# sloth_final.net
KiCad netlist of a schematic drawn in EAGLE
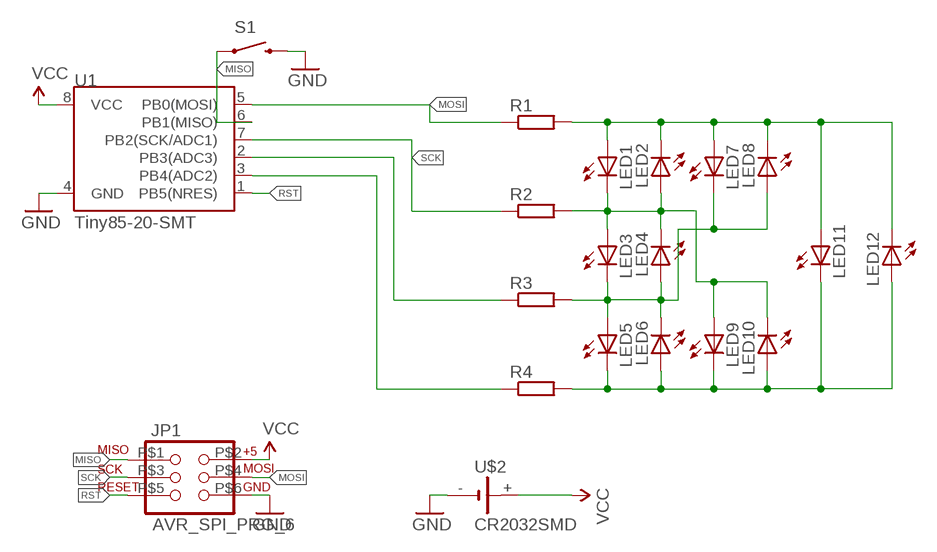
[diagram p0: schematic, sheet 1]

(export (version "E")
  (design (tool "Eeschema 10.0.6"))
  (components
    (comp (ref "JP1")
      (value "AVR_SPI_PRG_6")
      (footprint "eagle-import:2X3_SMD_PAD")
      (libsource (lib "eagle-import") (part "AVR_SPI_PRG_6"))
    )
    (comp (ref "LED1")
      (value "LEDCHIP-LED0805")
      (footprint "eagle-import:CHIP-LED0805")
      (libsource (lib "eagle-import") (part "LEDCHIP-LED0805"))
    )
    (comp (ref "LED2")
      (value "LEDCHIP-LED0805")
      (footprint "eagle-import:CHIP-LED0805")
      (libsource (lib "eagle-import") (part "LEDCHIP-LED0805"))
    )
    (comp (ref "LED3")
      (value "LEDCHIP-LED0805")
      (footprint "eagle-import:CHIP-LED0805")
      (libsource (lib "eagle-import") (part "LEDCHIP-LED0805"))
    )
    (comp (ref "LED4")
      (value "LEDCHIP-LED0805")
      (footprint "eagle-import:CHIP-LED0805")
      (libsource (lib "eagle-import") (part "LEDCHIP-LED0805"))
    )
    (comp (ref "LED5")
      (value "LEDCHIP-LED0805")
      (footprint "eagle-import:CHIP-LED0805")
      (libsource (lib "eagle-import") (part "LEDCHIP-LED0805"))
    )
    (comp (ref "LED6")
      (value "LEDCHIP-LED0805")
      (footprint "eagle-import:CHIP-LED0805")
      (libsource (lib "eagle-import") (part "LEDCHIP-LED0805"))
    )
    (comp (ref "LED7")
      (value "LEDCHIP-LED0805")
      (footprint "eagle-import:CHIP-LED0805")
      (libsource (lib "eagle-import") (part "LEDCHIP-LED0805"))
    )
    (comp (ref "LED8")
      (value "LEDCHIP-LED0805")
      (footprint "eagle-import:CHIP-LED0805")
      (libsource (lib "eagle-import") (part "LEDCHIP-LED0805"))
    )
    (comp (ref "LED9")
      (value "LEDCHIP-LED0805")
      (footprint "eagle-import:CHIP-LED0805")
      (libsource (lib "eagle-import") (part "LEDCHIP-LED0805"))
    )
    (comp (ref "LED10")
      (value "LEDCHIP-LED0805")
      (footprint "eagle-import:CHIP-LED0805")
      (libsource (lib "eagle-import") (part "LEDCHIP-LED0805"))
    )
    (comp (ref "LED11")
      (value "LEDCHIP-LED0805")
      (footprint "eagle-import:CHIP-LED0805")
      (libsource (lib "eagle-import") (part "LEDCHIP-LED0805"))
    )
    (comp (ref "LED12")
      (value "LEDCHIP-LED0805")
      (footprint "eagle-import:CHIP-LED0805")
      (libsource (lib "eagle-import") (part "LEDCHIP-LED0805"))
    )
    (comp (ref "R1")
      (value "R-EU_R0805")
      (footprint "eagle-import:R0805")
      (libsource (lib "eagle-import") (part "R-EU_R0805"))
    )
    (comp (ref "R2")
      (value "R-EU_R0805")
      (footprint "eagle-import:R0805")
      (libsource (lib "eagle-import") (part "R-EU_R0805"))
    )
    (comp (ref "R3")
      (value "R-EU_R0805")
      (footprint "eagle-import:R0805")
      (libsource (lib "eagle-import") (part "R-EU_R0805"))
    )
    (comp (ref "R4")
      (value "R-EU_R0805")
      (footprint "eagle-import:R0805")
      (libsource (lib "eagle-import") (part "R-EU_R0805"))
    )
    (comp (ref "S1")
      (value "SWITCH-MOMENTARY-2-SMD-1101NE")
      (footprint "eagle-import:TACTILE-SWITCH-1101NE")
      (libsource (lib "eagle-import") (part "SWITCH-MOMENTARY-2-SMD-1101NE"))
    )
    (comp (ref "U$2")
      (value "CR2032SMD")
      (footprint "eagle-import:CR2032SMD")
      (libsource (lib "eagle-import") (part "CR2032SMD"))
    )
    (comp (ref "U1")
      (value "Tiny85-20-SMT")
      (footprint "eagle-import:SO08-EIAJ")
      (libsource (lib "eagle-import") (part "ATTINY45TINY85-20-SMT"))
    )
  )
  (nets
    (net (code "1") (name "GND") (class "Default")
      (node (ref "JP1") (pin "P$6") (pinfunction "6_P$6") (pintype "passive"))
      (node (ref "S1") (pin "P$2") (pinfunction "2_P$2") (pintype "passive"))
      (node (ref "U$2") (pin "-") (pinfunction "-_-") (pintype "passive"))
      (node (ref "U1") (pin "4") (pinfunction "GND_4") (pintype "bidirectional"))
    )
    (net (code "2") (name "MISO") (class "Default")
      (node (ref "JP1") (pin "P$1") (pinfunction "1_P$1") (pintype "passive"))
      (node (ref "S1") (pin "P$1") (pinfunction "1_P$1") (pintype "passive"))
      (node (ref "U1") (pin "6") (pinfunction "PB1(MISO)_6") (pintype "bidirectional"))
    )
    (net (code "3") (name "MOSI") (class "Default")
      (node (ref "JP1") (pin "P$4") (pinfunction "4_P$4") (pintype "passive"))
      (node (ref "R1") (pin "1") (pinfunction "1_1") (pintype "passive"))
      (node (ref "U1") (pin "5") (pinfunction "PB0(MOSI)_5") (pintype "bidirectional"))
    )
    (net (code "4") (name "Net-(LED1-PadA)") (class "Default")
      (node (ref "LED1") (pin "A") (pinfunction "A_A") (pintype "passive"))
      (node (ref "LED11") (pin "A") (pinfunction "A_A") (pintype "passive"))
      (node (ref "LED12") (pin "C") (pinfunction "C_C") (pintype "passive"))
      (node (ref "LED2") (pin "C") (pinfunction "C_C") (pintype "passive"))
      (node (ref "LED7") (pin "A") (pinfunction "A_A") (pintype "passive"))
      (node (ref "LED8") (pin "C") (pinfunction "C_C") (pintype "passive"))
      (node (ref "R1") (pin "2") (pinfunction "2_2") (pintype "passive"))
    )
    (net (code "5") (name "Net-(LED1-PadC)") (class "Default")
      (node (ref "LED1") (pin "C") (pinfunction "C_C") (pintype "passive"))
      (node (ref "LED10") (pin "C") (pinfunction "C_C") (pintype "passive"))
      (node (ref "LED2") (pin "A") (pinfunction "A_A") (pintype "passive"))
      (node (ref "LED3") (pin "A") (pinfunction "A_A") (pintype "passive"))
      (node (ref "LED4") (pin "C") (pinfunction "C_C") (pintype "passive"))
      (node (ref "LED9") (pin "A") (pinfunction "A_A") (pintype "passive"))
      (node (ref "R2") (pin "2") (pinfunction "2_2") (pintype "passive"))
    )
    (net (code "6") (name "Net-(LED3-PadC)") (class "Default")
      (node (ref "LED3") (pin "C") (pinfunction "C_C") (pintype "passive"))
      (node (ref "LED4") (pin "A") (pinfunction "A_A") (pintype "passive"))
      (node (ref "LED5") (pin "A") (pinfunction "A_A") (pintype "passive"))
      (node (ref "LED6") (pin "C") (pinfunction "C_C") (pintype "passive"))
      (node (ref "LED7") (pin "C") (pinfunction "C_C") (pintype "passive"))
      (node (ref "LED8") (pin "A") (pinfunction "A_A") (pintype "passive"))
      (node (ref "R3") (pin "2") (pinfunction "2_2") (pintype "passive"))
    )
    (net (code "7") (name "Net-(LED10-PadA)") (class "Default")
      (node (ref "LED10") (pin "A") (pinfunction "A_A") (pintype "passive"))
      (node (ref "LED11") (pin "C") (pinfunction "C_C") (pintype "passive"))
      (node (ref "LED12") (pin "A") (pinfunction "A_A") (pintype "passive"))
      (node (ref "LED5") (pin "C") (pinfunction "C_C") (pintype "passive"))
      (node (ref "LED6") (pin "A") (pinfunction "A_A") (pintype "passive"))
      (node (ref "LED9") (pin "C") (pinfunction "C_C") (pintype "passive"))
      (node (ref "R4") (pin "2") (pinfunction "2_2") (pintype "passive"))
    )
    (net (code "8") (name "Net-(U1-PB3(ADC3))") (class "Default")
      (node (ref "R3") (pin "1") (pinfunction "1_1") (pintype "passive"))
      (node (ref "U1") (pin "2") (pinfunction "PB3(ADC3)_2") (pintype "bidirectional"))
    )
    (net (code "9") (name "Net-(U1-PB4(ADC2))") (class "Default")
      (node (ref "R4") (pin "1") (pinfunction "1_1") (pintype "passive"))
      (node (ref "U1") (pin "3") (pinfunction "PB4(ADC2)_3") (pintype "bidirectional"))
    )
    (net (code "10") (name "RST") (class "Default")
      (node (ref "JP1") (pin "P$5") (pinfunction "5_P$5") (pintype "passive"))
      (node (ref "U1") (pin "1") (pinfunction "PB5(NRES)_1") (pintype "bidirectional"))
    )
    (net (code "11") (name "SCK") (class "Default")
      (node (ref "JP1") (pin "P$3") (pinfunction "3_P$3") (pintype "passive"))
      (node (ref "R2") (pin "1") (pinfunction "1_1") (pintype "passive"))
      (node (ref "U1") (pin "7") (pinfunction "PB2(SCK/ADC1)_7") (pintype "bidirectional"))
    )
    (net (code "12") (name "VCC") (class "Default")
      (node (ref "JP1") (pin "P$2") (pinfunction "2_P$2") (pintype "passive"))
      (node (ref "U$2") (pin "+") (pinfunction "+_+") (pintype "passive"))
      (node (ref "U1") (pin "8") (pinfunction "VCC_8") (pintype "bidirectional"))
    )
  )
)
